# doodle_with_clock5_with_ftdi2_full_smd_v.net
KiCad netlist of a schematic drawn in EAGLE
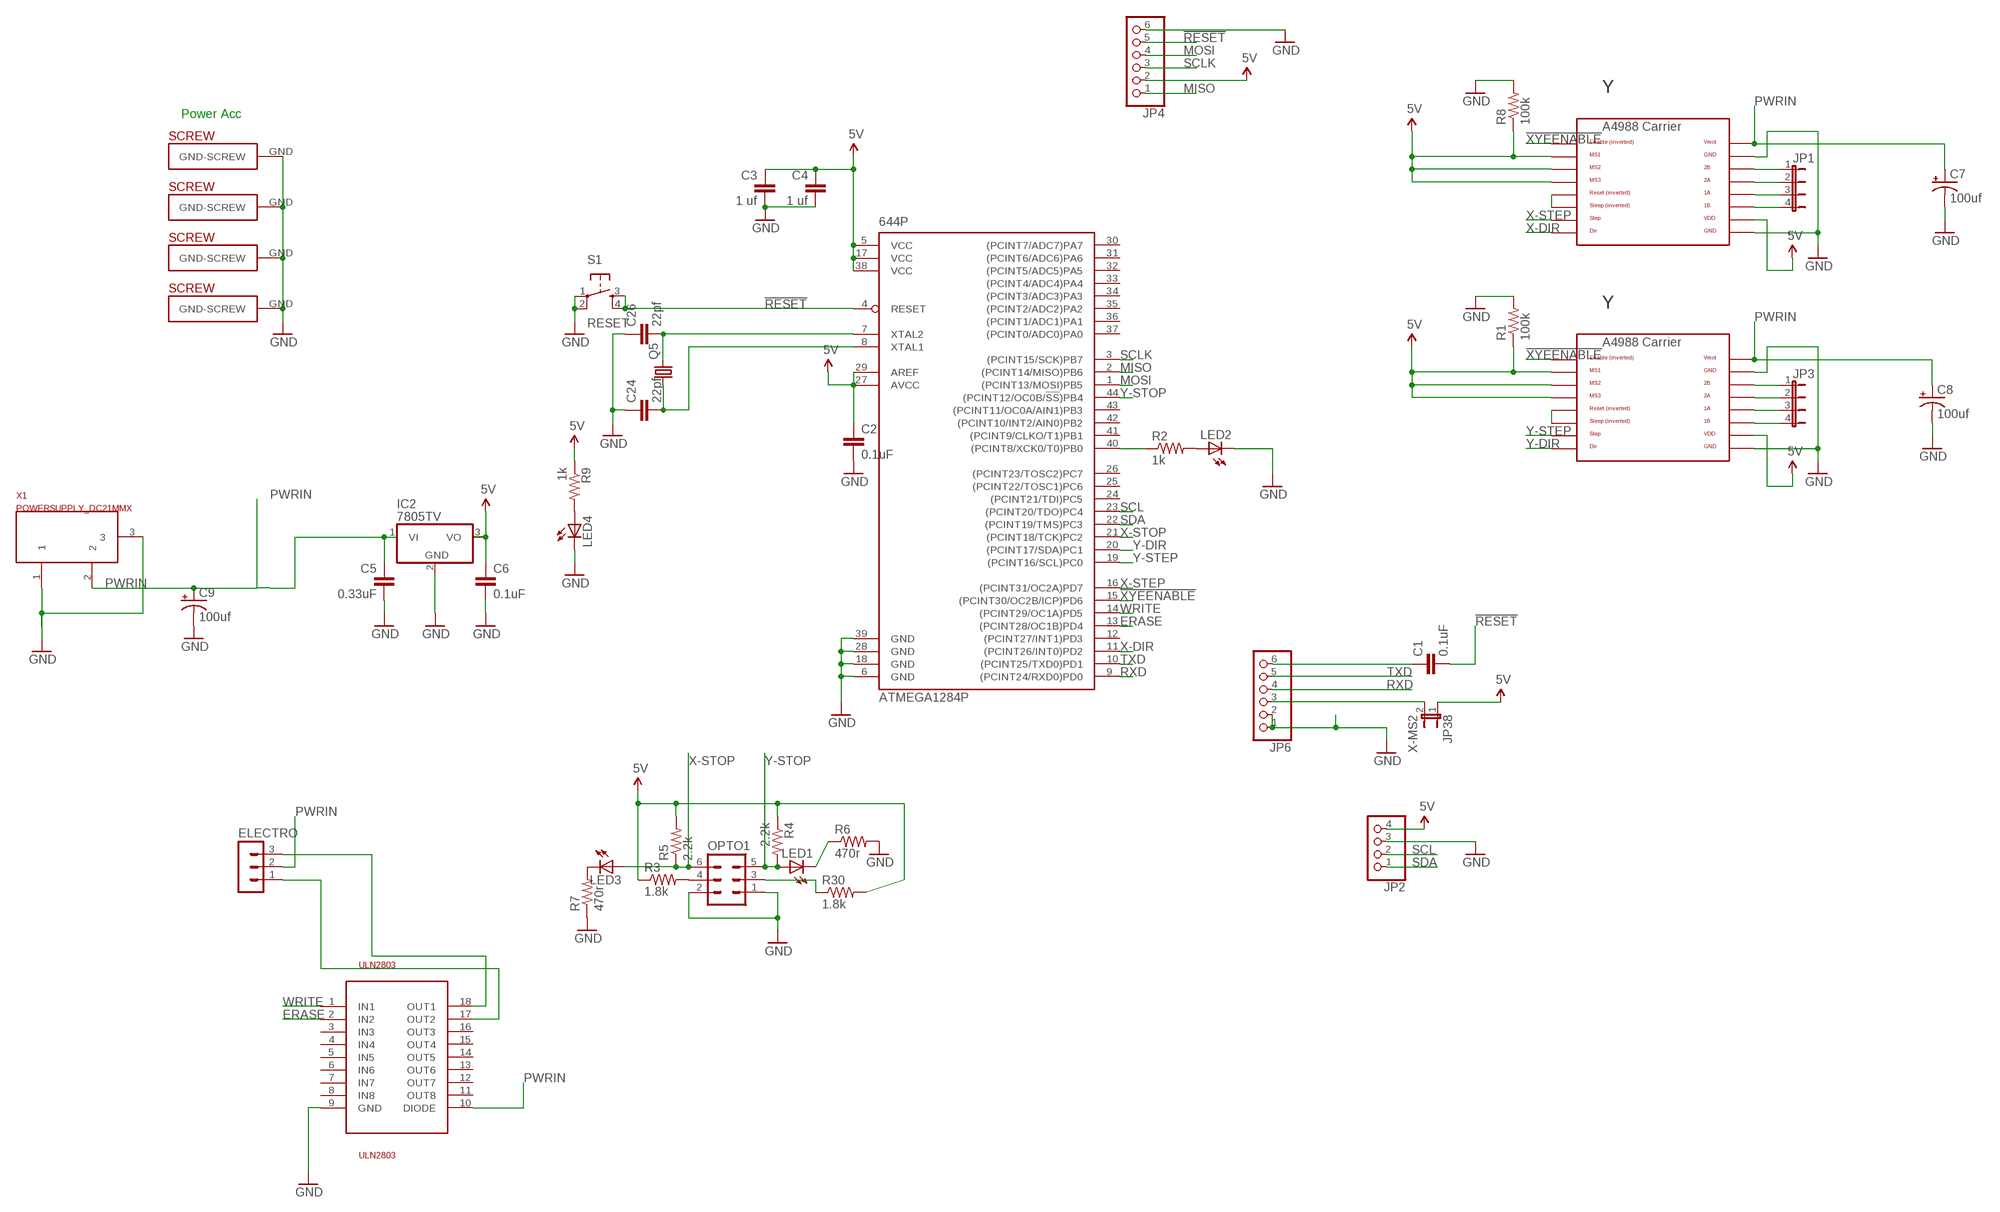
[diagram p0: schematic, sheet 1, part 1 of 2]
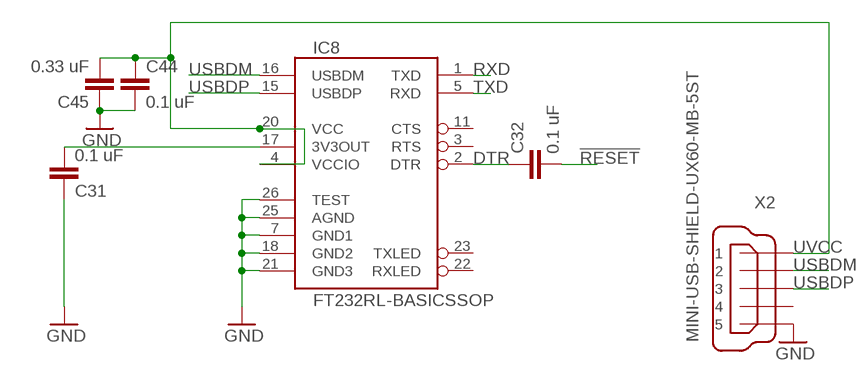
[diagram p1: schematic, sheet 1, part 2 of 2]

(export (version "E")
  (design (tool "Eeschema 10.0.6"))
  (components
    (comp (ref "644P")
      (value "ATMEGA1284P")
      (footprint "eagle-import:TQFP44")
      (fields (field (name "MPN") "ATMEGA644PV-10AU"))
      (libsource (lib "eagle-import") (part "ATMEGA644A"))
    )
    (comp (ref "C1")
      (value "0.1uF")
      (footprint "eagle-import:0805")
      (libsource (lib "eagle-import") (part "CAP0805"))
    )
    (comp (ref "C2")
      (value "0.1uF")
      (footprint "eagle-import:0805")
      (libsource (lib "eagle-import") (part "CAP0805"))
    )
    (comp (ref "C3")
      (value "1 uf")
      (footprint "eagle-import:0805")
      (libsource (lib "eagle-import") (part "CAP0805"))
    )
    (comp (ref "C4")
      (value "1 uf")
      (footprint "eagle-import:0805")
      (libsource (lib "eagle-import") (part "CAP0805"))
    )
    (comp (ref "C5")
      (value "0.33uF")
      (footprint "eagle-import:CAP-PTH-SMALL2")
      (libsource (lib "eagle-import") (part "CAPPTH2"))
    )
    (comp (ref "C6")
      (value "0.1uF")
      (footprint "eagle-import:CAP-PTH-SMALL2")
      (libsource (lib "eagle-import") (part "CAPPTH2"))
    )
    (comp (ref "C7")
      (value "100uf")
      (footprint "eagle-import:CPOL-RADIAL-100UF-25V")
      (libsource (lib "eagle-import") (part "CAP_POLPTH1"))
    )
    (comp (ref "C8")
      (value "100uf")
      (footprint "eagle-import:CPOL-RADIAL-100UF-25V")
      (libsource (lib "eagle-import") (part "CAP_POLPTH1"))
    )
    (comp (ref "C9")
      (value "100uf")
      (footprint "eagle-import:CPOL-RADIAL-100UF-25V")
      (libsource (lib "eagle-import") (part "CAP_POLPTH1"))
    )
    (comp (ref "C24")
      (value "22pf")
      (footprint "eagle-import:0805")
      (libsource (lib "eagle-import") (part "CAP0805"))
    )
    (comp (ref "C26")
      (value "22pf")
      (footprint "eagle-import:0805")
      (libsource (lib "eagle-import") (part "CAP0805"))
    )
    (comp (ref "C31")
      (value "0.1 uF")
      (footprint "eagle-import:C1206")
      (libsource (lib "eagle-import") (part "C-EUC1206"))
    )
    (comp (ref "C32")
      (value "0.1 uF")
      (footprint "eagle-import:C1206")
      (libsource (lib "eagle-import") (part "C-EUC1206"))
    )
    (comp (ref "C44")
      (value "0.1 uF")
      (footprint "eagle-import:C1206")
      (libsource (lib "eagle-import") (part "C-EUC1206"))
    )
    (comp (ref "C45")
      (value "0.33 uF")
      (footprint "eagle-import:C1206")
      (libsource (lib "eagle-import") (part "C-EUC1206"))
    )
    (comp (ref "ELECTRO")
      (value "MA03-1")
      (footprint "eagle-import:MA03-1")
      (libsource (lib "eagle-import") (part "MA03-1"))
    )
    (comp (ref "IC2")
      (value "7805TV")
      (footprint "eagle-import:TO220V")
      (libsource (lib "eagle-import") (part "78TV05"))
    )
    (comp (ref "IC8")
      (value "FT232RL-BASICSSOP")
      (footprint "eagle-import:SSOP28DB")
      (libsource (lib "eagle-import") (part "FT232RL-BASICSSOP"))
    )
    (comp (ref "JP1")
      (value "JP4E")
      (footprint "eagle-import:JP4")
      (libsource (lib "eagle-import") (part "JP4E"))
    )
    (comp (ref "JP2")
      (value "PINHD-1X4")
      (footprint "eagle-import:1X04")
      (libsource (lib "eagle-import") (part "PINHD-1X4"))
    )
    (comp (ref "JP3")
      (value "JP4E")
      (footprint "eagle-import:JP4")
      (libsource (lib "eagle-import") (part "JP4E"))
    )
    (comp (ref "JP4")
      (value "PINHD-1X6/90")
      (footprint "eagle-import:1X06_90")
      (libsource (lib "eagle-import") (part "PINHD-1X6/90"))
    )
    (comp (ref "JP6")
      (value "PINHD-1X6")
      (footprint "eagle-import:1X06")
      (libsource (lib "eagle-import") (part "PINHD-1X6"))
    )
    (comp (ref "JP38")
      (value "X-MS2")
      (footprint "eagle-import:1X02")
      (libsource (lib "eagle-import") (part "JUMPER-2PTH"))
    )
    (comp (ref "LED1")
      (value "LEDCHIPLED_0805")
      (footprint "eagle-import:CHIPLED_0805")
      (libsource (lib "eagle-import") (part "LEDCHIPLED_0805"))
    )
    (comp (ref "LED2")
      (value "LEDCHIPLED_0805")
      (footprint "eagle-import:CHIPLED_0805")
      (libsource (lib "eagle-import") (part "LEDCHIPLED_0805"))
    )
    (comp (ref "LED3")
      (value "LEDCHIPLED_0805")
      (footprint "eagle-import:CHIPLED_0805")
      (libsource (lib "eagle-import") (part "LEDCHIPLED_0805"))
    )
    (comp (ref "LED4")
      (value "LEDCHIPLED_0805")
      (footprint "eagle-import:CHIPLED_0805")
      (libsource (lib "eagle-import") (part "LEDCHIPLED_0805"))
    )
    (comp (ref "OPTO1")
      (value "MA03-2")
      (footprint "eagle-import:MA03-2")
      (libsource (lib "eagle-import") (part "MA03-2"))
    )
    (comp (ref "Q5")
      (value "CRYSTALHC49S")
      (footprint "eagle-import:HC49_S")
      (libsource (lib "eagle-import") (part "CRYSTALHC49S"))
    )
    (comp (ref "R1")
      (value "100k")
      (footprint "eagle-import:0207_7")
      (libsource (lib "eagle-import") (part "R-US_0207/7"))
    )
    (comp (ref "R2")
      (value "1k")
      (footprint "eagle-import:R0805")
      (libsource (lib "eagle-import") (part "resistor_R-US_R0805"))
    )
    (comp (ref "R3")
      (value "1.8k")
      (footprint "eagle-import:R0805")
      (libsource (lib "eagle-import") (part "resistor_R-US_R0805"))
    )
    (comp (ref "R4")
      (value "2.2k")
      (footprint "eagle-import:R0805")
      (libsource (lib "eagle-import") (part "resistor_R-US_R0805"))
    )
    (comp (ref "R5")
      (value "2.2k")
      (footprint "eagle-import:R0805")
      (libsource (lib "eagle-import") (part "resistor_R-US_R0805"))
    )
    (comp (ref "R6")
      (value "470r")
      (footprint "eagle-import:R0805")
      (libsource (lib "eagle-import") (part "resistor_R-US_R0805"))
    )
    (comp (ref "R7")
      (value "470r")
      (footprint "eagle-import:R0805")
      (libsource (lib "eagle-import") (part "resistor_R-US_R0805"))
    )
    (comp (ref "R8")
      (value "100k")
      (footprint "eagle-import:0207_7")
      (libsource (lib "eagle-import") (part "R-US_0207/7"))
    )
    (comp (ref "R9")
      (value "1k")
      (footprint "eagle-import:R0805")
      (libsource (lib "eagle-import") (part "resistor_R-US_R0805"))
    )
    (comp (ref "R30")
      (value "1.8k")
      (footprint "eagle-import:R0603")
      (libsource (lib "eagle-import") (part "resistor_R-US_R0603"))
    )
    (comp (ref "S1")
      (value "RESET")
      (footprint "eagle-import:TACTILE-PTH")
      (libsource (lib "eagle-import") (part "TAC_SWITCHPTH"))
    )
    (comp (ref "U$1")
      (value "A4988BREAKOUT")
      (footprint "eagle-import:A4988BREAKOUT")
      (libsource (lib "eagle-import") (part "A4988BREAKOUT"))
    )
    (comp (ref "U$7")
      (value "A4988BREAKOUT")
      (footprint "eagle-import:A4988BREAKOUT")
      (libsource (lib "eagle-import") (part "A4988BREAKOUT"))
    )
    (comp (ref "U$14")
      (value "PLATED-SCREW")
      (footprint "eagle-import:PLATEDSCREW")
      (libsource (lib "eagle-import") (part "PLATED-SCREW"))
    )
    (comp (ref "U$17")
      (value "PLATED-SCREW")
      (footprint "eagle-import:PLATEDSCREW")
      (libsource (lib "eagle-import") (part "PLATED-SCREW"))
    )
    (comp (ref "U$18")
      (value "PLATED-SCREW")
      (footprint "eagle-import:PLATEDSCREW")
      (libsource (lib "eagle-import") (part "PLATED-SCREW"))
    )
    (comp (ref "U$38")
      (value "PLATED-SCREW")
      (footprint "eagle-import:PLATEDSCREW")
      (libsource (lib "eagle-import") (part "PLATED-SCREW"))
    )
    (comp (ref "ULN2803")
      (value "ULN2803")
      (footprint "eagle-import:SO18L")
      (libsource (lib "eagle-import") (part "ULN2803"))
    )
    (comp (ref "X1")
      (value "POWERSUPPLY_DC21MMX")
      (footprint "eagle-import:POWERSUPPLY_DC-21MM")
      (libsource (lib "eagle-import") (part "POWERSUPPLY_DC21MMX"))
    )
    (comp (ref "X2")
      (value "MINI-USB-SHIELD-UX60-MB-5ST")
      (footprint "eagle-import:UX60-MB-5ST")
      (libsource (lib "eagle-import") (part "MINI-USB-SHIELD-UX60-MB-5ST"))
    )
  )
  (nets
    (net (code "1") (name "/DTR") (class "Default")
      (node (ref "C32") (pin "1") (pinfunction "1_1") (pintype "passive"))
      (node (ref "IC8") (pin "2") (pinfunction "DTR_2") (pintype "bidirectional"))
    )
    (net (code "2") (name "/ERASE") (class "Default")
      (node (ref "644P") (pin "13") (pinfunction "(PCINT28/OC1B)PD4_13") (pintype "bidirectional"))
      (node (ref "ULN2803") (pin "2") (pinfunction "IN2_2") (pintype "input"))
    )
    (net (code "3") (name "/MISO") (class "Default")
      (node (ref "644P") (pin "2") (pinfunction "(PCINT14/MISO)PB6_2") (pintype "bidirectional"))
      (node (ref "JP4") (pin "1") (pinfunction "1_1") (pintype "passive"))
    )
    (net (code "4") (name "/MOSI") (class "Default")
      (node (ref "644P") (pin "1") (pinfunction "(PCINT13/MOSI)PB5_1") (pintype "bidirectional"))
      (node (ref "JP4") (pin "4") (pinfunction "4_4") (pintype "passive"))
    )
    (net (code "5") (name "/PWRIN") (class "Default")
      (node (ref "C5") (pin "1") (pinfunction "1_1") (pintype "passive"))
      (node (ref "C7") (pin "1") (pinfunction "+_1") (pintype "passive"))
      (node (ref "C8") (pin "1") (pinfunction "+_1") (pintype "passive"))
      (node (ref "C9") (pin "1") (pinfunction "+_1") (pintype "passive"))
      (node (ref "ELECTRO") (pin "2") (pinfunction "2_2") (pintype "passive"))
      (node (ref "IC2") (pin "1") (pinfunction "VI_1") (pintype "input"))
      (node (ref "U$1") (pin "VMOT") (pinfunction "VMOT_VMOT") (pintype "power_in"))
      (node (ref "U$7") (pin "VMOT") (pinfunction "VMOT_VMOT") (pintype "power_in"))
      (node (ref "ULN2803") (pin "10") (pinfunction "DIODE_10") (pintype "power_in"))
      (node (ref "X1") (pin "2") (pinfunction "2_2") (pintype "power_in"))
    )
    (net (code "6") (name "/RXD") (class "Default")
      (node (ref "644P") (pin "9") (pinfunction "(PCINT24/RXD0)PD0_9") (pintype "bidirectional"))
      (node (ref "IC8") (pin "1") (pinfunction "TXD_1") (pintype "output"))
      (node (ref "JP6") (pin "4") (pinfunction "4_4") (pintype "passive"))
    )
    (net (code "7") (name "/SCL") (class "Default")
      (node (ref "644P") (pin "23") (pinfunction "(PCINT20/TDO)PC4_23") (pintype "output"))
      (node (ref "JP2") (pin "2") (pinfunction "2_2") (pintype "passive"))
    )
    (net (code "8") (name "/SCLK") (class "Default")
      (node (ref "644P") (pin "3") (pinfunction "(PCINT15/SCK)PB7_3") (pintype "bidirectional"))
      (node (ref "JP4") (pin "3") (pinfunction "3_3") (pintype "passive"))
    )
    (net (code "9") (name "/SDA") (class "Default")
      (node (ref "644P") (pin "22") (pinfunction "(PCINT19/TMS)PC3_22") (pintype "output"))
      (node (ref "JP2") (pin "1") (pinfunction "1_1") (pintype "passive"))
    )
    (net (code "10") (name "/TXD") (class "Default")
      (node (ref "644P") (pin "10") (pinfunction "(PCINT25/TXD0)PD1_10") (pintype "bidirectional"))
      (node (ref "IC8") (pin "5") (pinfunction "RXD_5") (pintype "input"))
      (node (ref "JP6") (pin "5") (pinfunction "5_5") (pintype "passive"))
    )
    (net (code "11") (name "/USBDM") (class "Default")
      (node (ref "IC8") (pin "16") (pinfunction "USBDM_16") (pintype "bidirectional"))
      (node (ref "X2") (pin "2") (pinfunction "2_2") (pintype "input"))
    )
    (net (code "12") (name "/USBDP") (class "Default")
      (node (ref "IC8") (pin "15") (pinfunction "USBDP_15") (pintype "bidirectional"))
      (node (ref "X2") (pin "3") (pinfunction "3_3") (pintype "input"))
    )
    (net (code "13") (name "/UVCC") (class "Default")
      (node (ref "C44") (pin "1") (pinfunction "1_1") (pintype "passive"))
      (node (ref "C45") (pin "2") (pinfunction "2_2") (pintype "passive"))
      (node (ref "IC8") (pin "20") (pinfunction "VCC_20") (pintype "power_in"))
      (node (ref "IC8") (pin "4") (pinfunction "VCCIO_4") (pintype "power_in"))
      (node (ref "X2") (pin "1") (pinfunction "1_1") (pintype "input"))
    )
    (net (code "14") (name "/WRITE") (class "Default")
      (node (ref "644P") (pin "14") (pinfunction "(PCINT29/OC1A)PD5_14") (pintype "bidirectional"))
      (node (ref "ULN2803") (pin "1") (pinfunction "IN1_1") (pintype "input"))
    )
    (net (code "15") (name "/X-DIR") (class "Default")
      (node (ref "644P") (pin "11") (pinfunction "(PCINT26/INT0)PD2_11") (pintype "bidirectional"))
      (node (ref "U$7") (pin "DIR") (pinfunction "DIR_DIR") (pintype "input"))
    )
    (net (code "16") (name "/X-STEP") (class "Default")
      (node (ref "644P") (pin "16") (pinfunction "(PCINT31/OC2A)PD7_16") (pintype "bidirectional"))
      (node (ref "U$7") (pin "STEP") (pinfunction "STEP_STEP") (pintype "input"))
    )
    (net (code "17") (name "/X-STOP") (class "Default")
      (node (ref "644P") (pin "21") (pinfunction "(PCINT18/TCK)PC2_21") (pintype "output"))
      (node (ref "LED3") (pin "A") (pinfunction "A_A") (pintype "passive"))
      (node (ref "OPTO1") (pin "6") (pinfunction "6_6") (pintype "passive"))
      (node (ref "R5") (pin "1") (pinfunction "1_1") (pintype "passive"))
    )
    (net (code "18") (name "/Y-DIR") (class "Default")
      (node (ref "644P") (pin "20") (pinfunction "(PCINT17/SDA)PC1_20") (pintype "output"))
      (node (ref "U$1") (pin "DIR") (pinfunction "DIR_DIR") (pintype "input"))
    )
    (net (code "19") (name "/Y-STEP") (class "Default")
      (node (ref "644P") (pin "19") (pinfunction "(PCINT16/SCL)PC0_19") (pintype "output"))
      (node (ref "U$1") (pin "STEP") (pinfunction "STEP_STEP") (pintype "input"))
    )
    (net (code "20") (name "/Y-STOP") (class "Default")
      (node (ref "644P") (pin "44") (pinfunction "(PCINT12/OC0B/~{SS})PB4_44") (pintype "bidirectional"))
      (node (ref "LED1") (pin "A") (pinfunction "A_A") (pintype "passive"))
      (node (ref "OPTO1") (pin "5") (pinfunction "5_5") (pintype "passive"))
      (node (ref "R4") (pin "2") (pinfunction "2_2") (pintype "passive"))
    )
    (net (code "21") (name "/~{RESET}") (class "Default")
      (node (ref "644P") (pin "4") (pinfunction "RESET_4") (pintype "input"))
      (node (ref "C1") (pin "2") (pinfunction "2_2") (pintype "passive"))
      (node (ref "C32") (pin "2") (pinfunction "2_2") (pintype "passive"))
      (node (ref "JP4") (pin "5") (pinfunction "5_5") (pintype "passive"))
      (node (ref "S1") (pin "3") (pinfunction "3_3") (pintype "passive"))
      (node (ref "S1") (pin "4") (pinfunction "4_4") (pintype "passive"))
    )
    (net (code "22") (name "/~{XYEENABLE}") (class "Default")
      (node (ref "644P") (pin "15") (pinfunction "(PCINT30/OC2B/ICP)PD6_15") (pintype "bidirectional"))
      (node (ref "U$1") (pin "EN") (pinfunction "EN_EN") (pintype "input"))
      (node (ref "U$7") (pin "EN") (pinfunction "EN_EN") (pintype "input"))
    )
    (net (code "23") (name "5V") (class "Default")
      (node (ref "644P") (pin "17") (pinfunction "VCC_17") (pintype "power_in"))
      (node (ref "644P") (pin "27") (pinfunction "AVCC_27") (pintype "power_in"))
      (node (ref "644P") (pin "29") (pinfunction "AREF_29") (pintype "passive"))
      (node (ref "644P") (pin "38") (pinfunction "VCC_38") (pintype "power_in"))
      (node (ref "644P") (pin "5") (pinfunction "VCC_5") (pintype "power_in"))
      (node (ref "C2") (pin "1") (pinfunction "1_1") (pintype "passive"))
      (node (ref "C3") (pin "1") (pinfunction "1_1") (pintype "passive"))
      (node (ref "C4") (pin "1") (pinfunction "1_1") (pintype "passive"))
      (node (ref "C6") (pin "1") (pinfunction "1_1") (pintype "passive"))
      (node (ref "IC2") (pin "3") (pinfunction "VO_3") (pintype "passive"))
      (node (ref "JP2") (pin "4") (pinfunction "4_4") (pintype "passive"))
      (node (ref "JP38") (pin "1") (pinfunction "1_1") (pintype "passive"))
      (node (ref "JP4") (pin "2") (pinfunction "2_2") (pintype "passive"))
      (node (ref "R1") (pin "1") (pinfunction "1_1") (pintype "passive"))
      (node (ref "R3") (pin "1") (pinfunction "1_1") (pintype "passive"))
      (node (ref "R30") (pin "2") (pinfunction "2_2") (pintype "passive"))
      (node (ref "R4") (pin "1") (pinfunction "1_1") (pintype "passive"))
      (node (ref "R5") (pin "2") (pinfunction "2_2") (pintype "passive"))
      (node (ref "R8") (pin "1") (pinfunction "1_1") (pintype "passive"))
      (node (ref "R9") (pin "1") (pinfunction "1_1") (pintype "passive"))
      (node (ref "U$1") (pin "MS1") (pinfunction "MS1_MS1") (pintype "input"))
      (node (ref "U$1") (pin "MS2") (pinfunction "MS2_MS2") (pintype "input"))
      (node (ref "U$1") (pin "MS3") (pinfunction "MS3_MS3") (pintype "input"))
      (node (ref "U$1") (pin "VDD") (pinfunction "VDD_VDD") (pintype "power_in"))
      (node (ref "U$7") (pin "MS1") (pinfunction "MS1_MS1") (pintype "input"))
      (node (ref "U$7") (pin "MS2") (pinfunction "MS2_MS2") (pintype "input"))
      (node (ref "U$7") (pin "MS3") (pinfunction "MS3_MS3") (pintype "input"))
      (node (ref "U$7") (pin "VDD") (pinfunction "VDD_VDD") (pintype "power_in"))
    )
    (net (code "24") (name "GND") (class "Default")
      (node (ref "644P") (pin "18") (pinfunction "GND_18") (pintype "power_in"))
      (node (ref "644P") (pin "28") (pinfunction "GND_28") (pintype "power_in"))
      (node (ref "644P") (pin "39") (pinfunction "GND_39") (pintype "power_in"))
      (node (ref "644P") (pin "6") (pinfunction "GND_6") (pintype "power_in"))
      (node (ref "C2") (pin "2") (pinfunction "2_2") (pintype "passive"))
      (node (ref "C24") (pin "1") (pinfunction "1_1") (pintype "passive"))
      (node (ref "C26") (pin "1") (pinfunction "1_1") (pintype "passive"))
      (node (ref "C3") (pin "2") (pinfunction "2_2") (pintype "passive"))
      (node (ref "C31") (pin "1") (pinfunction "1_1") (pintype "passive"))
      (node (ref "C4") (pin "2") (pinfunction "2_2") (pintype "passive"))
      (node (ref "C44") (pin "2") (pinfunction "2_2") (pintype "passive"))
      (node (ref "C45") (pin "1") (pinfunction "1_1") (pintype "passive"))
      (node (ref "C5") (pin "2") (pinfunction "2_2") (pintype "passive"))
      (node (ref "C6") (pin "2") (pinfunction "2_2") (pintype "passive"))
      (node (ref "C7") (pin "2") (pinfunction "-_2") (pintype "passive"))
      (node (ref "C8") (pin "2") (pinfunction "-_2") (pintype "passive"))
      (node (ref "C9") (pin "2") (pinfunction "-_2") (pintype "passive"))
      (node (ref "IC2") (pin "2") (pinfunction "GND_2") (pintype "passive"))
      (node (ref "IC8") (pin "18") (pinfunction "GND2_18") (pintype "power_in"))
      (node (ref "IC8") (pin "21") (pinfunction "GND3_21") (pintype "power_in"))
      (node (ref "IC8") (pin "25") (pinfunction "AGND_25") (pintype "power_in"))
      (node (ref "IC8") (pin "26") (pinfunction "TEST_26") (pintype "input"))
      (node (ref "IC8") (pin "7") (pinfunction "GND1_7") (pintype "power_in"))
      (node (ref "JP2") (pin "3") (pinfunction "3_3") (pintype "passive"))
      (node (ref "JP4") (pin "6") (pinfunction "6_6") (pintype "passive"))
      (node (ref "JP6") (pin "1") (pinfunction "1_1") (pintype "passive"))
      (node (ref "JP6") (pin "2") (pinfunction "2_2") (pintype "passive"))
      (node (ref "LED2") (pin "C") (pinfunction "C_C") (pintype "passive"))
      (node (ref "LED4") (pin "C") (pinfunction "C_C") (pintype "passive"))
      (node (ref "OPTO1") (pin "1") (pinfunction "1_1") (pintype "passive"))
      (node (ref "OPTO1") (pin "2") (pinfunction "2_2") (pintype "passive"))
      (node (ref "R1") (pin "2") (pinfunction "2_2") (pintype "passive"))
      (node (ref "R6") (pin "2") (pinfunction "2_2") (pintype "passive"))
      (node (ref "R7") (pin "1") (pinfunction "1_1") (pintype "passive"))
      (node (ref "R8") (pin "2") (pinfunction "2_2") (pintype "passive"))
      (node (ref "S1") (pin "1") (pinfunction "1_1") (pintype "passive"))
      (node (ref "S1") (pin "2") (pinfunction "2_2") (pintype "passive"))
      (node (ref "U$1") (pin "GND") (pinfunction "GND_GND") (pintype "power_in"))
      (node (ref "U$1") (pin "GND@0") (pinfunction "GND_GND@0") (pintype "power_in"))
      (node (ref "U$14") (pin "GND") (pinfunction "GND-SCREW_GND") (pintype "bidirectional"))
      (node (ref "U$17") (pin "GND") (pinfunction "GND-SCREW_GND") (pintype "bidirectional"))
      (node (ref "U$18") (pin "GND") (pinfunction "GND-SCREW_GND") (pintype "bidirectional"))
      (node (ref "U$38") (pin "GND") (pinfunction "GND-SCREW_GND") (pintype "bidirectional"))
      (node (ref "U$7") (pin "GND") (pinfunction "GND_GND") (pintype "power_in"))
      (node (ref "U$7") (pin "GND@0") (pinfunction "GND_GND@0") (pintype "power_in"))
      (node (ref "ULN2803") (pin "9") (pinfunction "GND_9") (pintype "power_in"))
      (node (ref "X1") (pin "1") (pinfunction "1_1") (pintype "power_in"))
      (node (ref "X1") (pin "3") (pinfunction "3_3") (pintype "power_in"))
      (node (ref "X2") (pin "5") (pinfunction "5_5") (pintype "input"))
    )
    (net (code "25") (name "Net-(644P-(PCINT8{slash}XCK0{slash}T0)PB0)") (class "Default")
      (node (ref "644P") (pin "40") (pinfunction "(PCINT8/XCK0/T0)PB0_40") (pintype "bidirectional"))
      (node (ref "R2") (pin "1") (pinfunction "1_1") (pintype "passive"))
    )
    (net (code "26") (name "Net-(644P-XTAL1)") (class "Default")
      (node (ref "644P") (pin "8") (pinfunction "XTAL1_8") (pintype "bidirectional"))
      (node (ref "C24") (pin "2") (pinfunction "2_2") (pintype "passive"))
      (node (ref "Q5") (pin "1") (pinfunction "1_1") (pintype "passive"))
    )
    (net (code "27") (name "Net-(644P-XTAL2)") (class "Default")
      (node (ref "644P") (pin "7") (pinfunction "XTAL2_7") (pintype "bidirectional"))
      (node (ref "C26") (pin "2") (pinfunction "2_2") (pintype "passive"))
      (node (ref "Q5") (pin "2") (pinfunction "2_2") (pintype "passive"))
    )
    (net (code "28") (name "Net-(C1-Pad1)") (class "Default")
      (node (ref "C1") (pin "1") (pinfunction "1_1") (pintype "passive"))
      (node (ref "JP6") (pin "6") (pinfunction "6_6") (pintype "passive"))
    )
    (net (code "29") (name "Net-(IC8-3V3OUT)") (class "Default")
      (node (ref "C31") (pin "2") (pinfunction "2_2") (pintype "passive"))
      (node (ref "IC8") (pin "17") (pinfunction "3V3OUT_17") (pintype "output"))
    )
    (net (code "30") (name "Net-(JP1-Pad1)") (class "Default")
      (node (ref "JP1") (pin "1") (pinfunction "1_1") (pintype "passive"))
      (node (ref "U$7") (pin "2B") (pinfunction "2B_2B") (pintype "output"))
    )
    (net (code "31") (name "Net-(JP1-Pad2)") (class "Default")
      (node (ref "JP1") (pin "2") (pinfunction "2_2") (pintype "passive"))
      (node (ref "U$7") (pin "2A") (pinfunction "2A_2A") (pintype "output"))
    )
    (net (code "32") (name "Net-(JP1-Pad3)") (class "Default")
      (node (ref "JP1") (pin "3") (pinfunction "3_3") (pintype "passive"))
      (node (ref "U$7") (pin "1A") (pinfunction "1A_1A") (pintype "output"))
    )
    (net (code "33") (name "Net-(JP1-Pad4)") (class "Default")
      (node (ref "JP1") (pin "4") (pinfunction "4_4") (pintype "passive"))
      (node (ref "U$7") (pin "1B") (pinfunction "1B_1B") (pintype "output"))
    )
    (net (code "34") (name "Net-(JP3-Pad1)") (class "Default")
      (node (ref "JP3") (pin "1") (pinfunction "1_1") (pintype "passive"))
      (node (ref "U$1") (pin "2B") (pinfunction "2B_2B") (pintype "output"))
    )
    (net (code "35") (name "Net-(JP3-Pad2)") (class "Default")
      (node (ref "JP3") (pin "2") (pinfunction "2_2") (pintype "passive"))
      (node (ref "U$1") (pin "2A") (pinfunction "2A_2A") (pintype "output"))
    )
    (net (code "36") (name "Net-(JP3-Pad3)") (class "Default")
      (node (ref "JP3") (pin "3") (pinfunction "3_3") (pintype "passive"))
      (node (ref "U$1") (pin "1A") (pinfunction "1A_1A") (pintype "output"))
    )
    (net (code "37") (name "Net-(JP3-Pad4)") (class "Default")
      (node (ref "JP3") (pin "4") (pinfunction "4_4") (pintype "passive"))
      (node (ref "U$1") (pin "1B") (pinfunction "1B_1B") (pintype "output"))
    )
    (net (code "38") (name "Net-(JP38-Pad2)") (class "Default")
      (node (ref "JP38") (pin "2") (pinfunction "2_2") (pintype "passive"))
      (node (ref "JP6") (pin "3") (pinfunction "3_3") (pintype "passive"))
    )
    (net (code "39") (name "Net-(LED1-PadC)") (class "Default")
      (node (ref "LED1") (pin "C") (pinfunction "C_C") (pintype "passive"))
      (node (ref "R6") (pin "1") (pinfunction "1_1") (pintype "passive"))
    )
    (net (code "40") (name "Net-(LED2-PadA)") (class "Default")
      (node (ref "LED2") (pin "A") (pinfunction "A_A") (pintype "passive"))
      (node (ref "R2") (pin "2") (pinfunction "2_2") (pintype "passive"))
    )
    (net (code "41") (name "Net-(LED3-PadC)") (class "Default")
      (node (ref "LED3") (pin "C") (pinfunction "C_C") (pintype "passive"))
      (node (ref "R7") (pin "2") (pinfunction "2_2") (pintype "passive"))
    )
    (net (code "42") (name "Net-(LED4-PadA)") (class "Default")
      (node (ref "LED4") (pin "A") (pinfunction "A_A") (pintype "passive"))
      (node (ref "R9") (pin "2") (pinfunction "2_2") (pintype "passive"))
    )
    (net (code "43") (name "Net-(OPTO1-Pad3)") (class "Default")
      (node (ref "OPTO1") (pin "3") (pinfunction "3_3") (pintype "passive"))
      (node (ref "R30") (pin "1") (pinfunction "1_1") (pintype "passive"))
    )
    (net (code "44") (name "Net-(OPTO1-Pad4)") (class "Default")
      (node (ref "OPTO1") (pin "4") (pinfunction "4_4") (pintype "passive"))
      (node (ref "R3") (pin "2") (pinfunction "2_2") (pintype "passive"))
    )
    (net (code "45") (name "Net-(U$1-SLEEP)") (class "Default")
      (node (ref "U$1") (pin "RST") (pinfunction "RST_RST") (pintype "input"))
      (node (ref "U$1") (pin "SLP") (pinfunction "SLEEP_SLP") (pintype "input"))
    )
    (net (code "46") (name "Net-(U$7-SLEEP)") (class "Default")
      (node (ref "U$7") (pin "RST") (pinfunction "RST_RST") (pintype "input"))
      (node (ref "U$7") (pin "SLP") (pinfunction "SLEEP_SLP") (pintype "input"))
    )
    (net (code "47") (name "Net-(ULN2803-OUT1)") (class "Default")
      (node (ref "ELECTRO") (pin "3") (pinfunction "3_3") (pintype "passive"))
      (node (ref "ULN2803") (pin "18") (pinfunction "OUT1_18") (pintype "open_collector"))
    )
    (net (code "48") (name "Net-(ULN2803-OUT2)") (class "Default")
      (node (ref "ELECTRO") (pin "1") (pinfunction "1_1") (pintype "passive"))
      (node (ref "ULN2803") (pin "17") (pinfunction "OUT2_17") (pintype "open_collector"))
    )
    (net (code "49") (name "unconnected-(644P-(PCINT0{slash}ADC0)PA0-Pad37)") (class "Default")
      (node (ref "644P") (pin "37") (pinfunction "(PCINT0/ADC0)PA0_37") (pintype "bidirectional"))
    )
    (net (code "50") (name "unconnected-(644P-(PCINT1{slash}ADC1)PA1-Pad36)") (class "Default")
      (node (ref "644P") (pin "36") (pinfunction "(PCINT1/ADC1)PA1_36") (pintype "bidirectional"))
    )
    (net (code "51") (name "unconnected-(644P-(PCINT2{slash}ADC2)PA2-Pad35)") (class "Default")
      (node (ref "644P") (pin "35") (pinfunction "(PCINT2/ADC2)PA2_35") (pintype "bidirectional"))
    )
    (net (code "52") (name "unconnected-(644P-(PCINT3{slash}ADC3)PA3-Pad34)") (class "Default")
      (node (ref "644P") (pin "34") (pinfunction "(PCINT3/ADC3)PA3_34") (pintype "bidirectional"))
    )
    (net (code "53") (name "unconnected-(644P-(PCINT4{slash}ADC4)PA4-Pad33)") (class "Default")
      (node (ref "644P") (pin "33") (pinfunction "(PCINT4/ADC4)PA4_33") (pintype "bidirectional"))
    )
    (net (code "54") (name "unconnected-(644P-(PCINT5{slash}ADC5)PA5-Pad32)") (class "Default")
      (node (ref "644P") (pin "32") (pinfunction "(PCINT5/ADC5)PA5_32") (pintype "bidirectional"))
    )
    (net (code "55") (name "unconnected-(644P-(PCINT6{slash}ADC6)PA6-Pad31)") (class "Default")
      (node (ref "644P") (pin "31") (pinfunction "(PCINT6/ADC6)PA6_31") (pintype "bidirectional"))
    )
    (net (code "56") (name "unconnected-(644P-(PCINT7{slash}ADC7)PA7-Pad30)") (class "Default")
      (node (ref "644P") (pin "30") (pinfunction "(PCINT7/ADC7)PA7_30") (pintype "bidirectional"))
    )
    (net (code "57") (name "unconnected-(644P-(PCINT9{slash}CLKO{slash}T1)PB1-Pad41)") (class "Default")
      (node (ref "644P") (pin "41") (pinfunction "(PCINT9/CLKO/T1)PB1_41") (pintype "bidirectional"))
    )
    (net (code "58") (name "unconnected-(644P-(PCINT10{slash}INT2{slash}AIN0)PB2-Pad42)") (class "Default")
      (node (ref "644P") (pin "42") (pinfunction "(PCINT10/INT2/AIN0)PB2_42") (pintype "bidirectional"))
    )
    (net (code "59") (name "unconnected-(644P-(PCINT11{slash}OC0A{slash}AIN1)PB3-Pad43)") (class "Default")
      (node (ref "644P") (pin "43") (pinfunction "(PCINT11/OC0A/AIN1)PB3_43") (pintype "bidirectional"))
    )
    (net (code "60") (name "unconnected-(644P-(PCINT21{slash}TDI)PC5-Pad24)") (class "Default")
      (node (ref "644P") (pin "24") (pinfunction "(PCINT21/TDI)PC5_24") (pintype "output"))
    )
    (net (code "61") (name "unconnected-(644P-(PCINT22{slash}TOSC1)PC6-Pad25)") (class "Default")
      (node (ref "644P") (pin "25") (pinfunction "(PCINT22/TOSC1)PC6_25") (pintype "output"))
    )
    (net (code "62") (name "unconnected-(644P-(PCINT23{slash}TOSC2)PC7-Pad26)") (class "Default")
      (node (ref "644P") (pin "26") (pinfunction "(PCINT23/TOSC2)PC7_26") (pintype "output"))
    )
    (net (code "63") (name "unconnected-(644P-(PCINT27{slash}INT1)PD3-Pad12)") (class "Default")
      (node (ref "644P") (pin "12") (pinfunction "(PCINT27/INT1)PD3_12") (pintype "bidirectional"))
    )
    (net (code "64") (name "unconnected-(IC8-CTS-Pad11)") (class "Default")
      (node (ref "IC8") (pin "11") (pinfunction "CTS_11") (pintype "bidirectional"))
    )
    (net (code "65") (name "unconnected-(IC8-RTS-Pad3)") (class "Default")
      (node (ref "IC8") (pin "3") (pinfunction "RTS_3") (pintype "bidirectional"))
    )
    (net (code "66") (name "unconnected-(IC8-RXLED-Pad22)") (class "Default")
      (node (ref "IC8") (pin "22") (pinfunction "RXLED_22") (pintype "bidirectional"))
    )
    (net (code "67") (name "unconnected-(IC8-TXLED-Pad23)") (class "Default")
      (node (ref "IC8") (pin "23") (pinfunction "TXLED_23") (pintype "bidirectional"))
    )
    (net (code "68") (name "unconnected-(ULN2803-IN3-Pad3)") (class "Default")
      (node (ref "ULN2803") (pin "3") (pinfunction "IN3_3") (pintype "input"))
    )
    (net (code "69") (name "unconnected-(ULN2803-IN4-Pad4)") (class "Default")
      (node (ref "ULN2803") (pin "4") (pinfunction "IN4_4") (pintype "input"))
    )
    (net (code "70") (name "unconnected-(ULN2803-IN5-Pad5)") (class "Default")
      (node (ref "ULN2803") (pin "5") (pinfunction "IN5_5") (pintype "input"))
    )
    (net (code "71") (name "unconnected-(ULN2803-IN6-Pad6)") (class "Default")
      (node (ref "ULN2803") (pin "6") (pinfunction "IN6_6") (pintype "input"))
    )
    (net (code "72") (name "unconnected-(ULN2803-IN7-Pad7)") (class "Default")
      (node (ref "ULN2803") (pin "7") (pinfunction "IN7_7") (pintype "input"))
    )
    (net (code "73") (name "unconnected-(ULN2803-IN8-Pad8)") (class "Default")
      (node (ref "ULN2803") (pin "8") (pinfunction "IN8_8") (pintype "input"))
    )
    (net (code "74") (name "unconnected-(ULN2803-OUT3-Pad16)") (class "Default")
      (node (ref "ULN2803") (pin "16") (pinfunction "OUT3_16") (pintype "open_collector"))
    )
    (net (code "75") (name "unconnected-(ULN2803-OUT4-Pad15)") (class "Default")
      (node (ref "ULN2803") (pin "15") (pinfunction "OUT4_15") (pintype "open_collector"))
    )
    (net (code "76") (name "unconnected-(ULN2803-OUT5-Pad14)") (class "Default")
      (node (ref "ULN2803") (pin "14") (pinfunction "OUT5_14") (pintype "open_collector"))
    )
    (net (code "77") (name "unconnected-(ULN2803-OUT6-Pad13)") (class "Default")
      (node (ref "ULN2803") (pin "13") (pinfunction "OUT6_13") (pintype "open_collector"))
    )
    (net (code "78") (name "unconnected-(ULN2803-OUT7-Pad12)") (class "Default")
      (node (ref "ULN2803") (pin "12") (pinfunction "OUT7_12") (pintype "open_collector"))
    )
    (net (code "79") (name "unconnected-(ULN2803-OUT8-Pad11)") (class "Default")
      (node (ref "ULN2803") (pin "11") (pinfunction "OUT8_11") (pintype "open_collector"))
    )
    (net (code "80") (name "unconnected-(X2-Pad4)") (class "Default")
      (node (ref "X2") (pin "4") (pinfunction "4_4") (pintype "input"))
    )
  )
)
